# Single-ADC_ADS1252U.net
KiCad netlist of a schematic drawn in Altium Designer
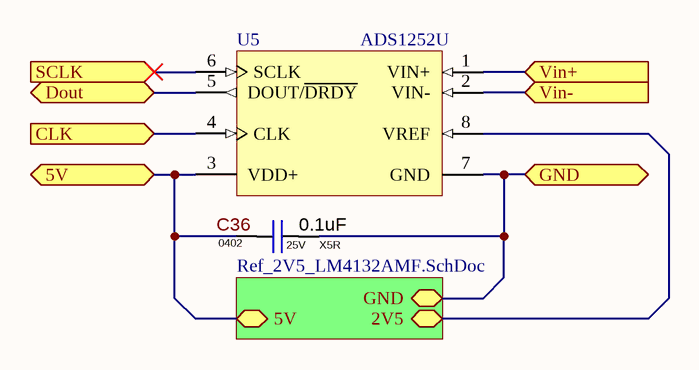
[diagram p0: Single-ADC_ADS1252U.SchDoc]

(export (version "E")
  (design (tool "Eeschema 10.0.6"))
  (components
    (comp (ref "C36")
      (value "0.1uF")
      (footprint "C_CERAMIC_0402_HI")
      (description "100nF 25V X5R ±10% 0402 Ceramic Capacitor RoHS")
      (fields
        (field (name "PACKAGE") "0402")
        (field (name "VOLTAGE") "25V")
        (field (name "DIELECTRIC TYPE") "X5R")
        (field (name "PART NUMBER") "CL05A104KA5NNNC")
        (field (name "MANUFACTURER") "Samsung Electro-Mechanics")
      )
      (libsource (lib "EL.XXX.T01") (part "CL05A104KA5NNNC"))
    )
    (comp (ref "U5")
      (value "ADS1252U")
      (footprint "TI-D8_M")
      (description "ResolutionPlus 24-Bit, 40 kHz ADC, -40 to 85 degC, 8-pin SOIC (D8), Green (RoHS & no Sb/Br)")
      (fields (field (name "MANUFACTURER") "Texas Instruments"))
      (libsource (lib "EL.XXX.T01") (part "CMP-0003-00072-2"))
    )
  )
  (nets
    (net (code "1") (name "/2V5") (class "Default")
      (node (ref "U5") (pin "8") (pinfunction "VREF_8") (pintype "input"))
    )
    (net (code "2") (name "/5V") (class "Default")
      (node (ref "C36") (pin "1") (pinfunction "1_1") (pintype "passive"))
      (node (ref "U5") (pin "3") (pinfunction "VDD+_3") (pintype "power_in"))
    )
    (net (code "3") (name "/CLK") (class "Default")
      (node (ref "U5") (pin "4") (pinfunction "CLK_4") (pintype "input"))
    )
    (net (code "4") (name "/Dout") (class "Default")
      (node (ref "U5") (pin "5") (pinfunction "DOUT/~{DRDY}_5") (pintype "output"))
    )
    (net (code "5") (name "/GND") (class "Default")
      (node (ref "C36") (pin "2") (pinfunction "2_2") (pintype "passive"))
      (node (ref "U5") (pin "7") (pinfunction "GND_7") (pintype "power_in"))
    )
    (net (code "6") (name "/SCLK") (class "Default")
      (node (ref "U5") (pin "6") (pinfunction "SCLK_6") (pintype "input+no_connect"))
    )
    (net (code "7") (name "/Vin+") (class "Default")
      (node (ref "U5") (pin "1") (pinfunction "VIN+_1") (pintype "input"))
    )
    (net (code "8") (name "/Vin-") (class "Default")
      (node (ref "U5") (pin "2") (pinfunction "VIN-_2") (pintype "input"))
    )
  )
)
